# LCD.net
KiCad netlist of a schematic drawn in Altium Designer
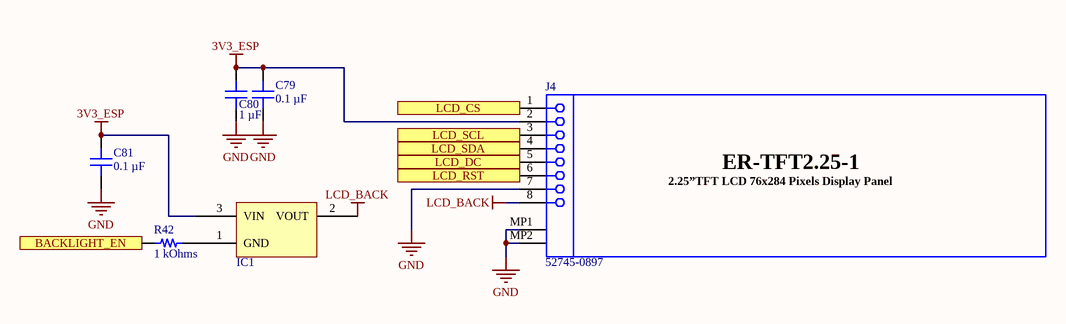
[diagram p0: LCD.SchDoc]

(export (version "E")
  (design (tool "Eeschema 10.0.6"))
  (components
    (comp (ref "C79")
      (value "0.1 µF")
      (footprint "CAP 0603_1608")
      (description "SMT Capacitor")
      (fields (field (name "PART NUMBER") "C0603C104M5RACTU") (field (name "MANUFACTURER") "KEMET"))
      (libsource (lib "Altium DB") (part "Capacitor"))
    )
    (comp (ref "C80")
      (value "1 µF")
      (footprint "CAP 0603_1608")
      (description "SMT Capacitor")
      (fields
        (field (name "PART NUMBER") "GMC10X7R105M50NT")
        (field (name "MANUFACTURER") "Cal-Chip Electronics, Inc.")
      )
      (libsource (lib "Altium DB") (part "Capacitor"))
    )
    (comp (ref "C81")
      (value "0.1 µF")
      (footprint "CAP 0603_1608")
      (description "SMT Capacitor")
      (fields (field (name "PART NUMBER") "C0603C104M5RACTU") (field (name "MANUFACTURER") "KEMET"))
      (libsource (lib "Altium DB") (part "Capacitor"))
    )
    (comp (ref "IC1")
      (value "Taken From Chinese PCB")
      (footprint "DIODES SOT-23-3")
      (description "IC REG LINEAR LED DRIVER 60mA")
      (fields (field (name "MANUFACTURER") "Diodes Incorporated"))
      (libsource (lib "Altium DB") (part "Diodes Inc AP7313R"))
    )
    (comp (ref "J4")
      (value "52745-0897")
      (footprint "MOLX-52745-0897")
      (fields (field (name "MANUFACTURER") "Molex"))
      (libsource (lib "Lib") (part "52745-0897"))
    )
    (comp (ref "R42")
      (value "1 kOhms")
      (footprint "RES 0603_1608")
      (description "RES SMD 1K OHM 1% 1/3W 0603")
      (fields
        (field (name "MANUFACTURER") "Panasonic Electronic Components")
        (field (name "PART NUMBER") "ERJ-PA3F1001V")
      )
      (libsource (lib "Altium DB") (part "Resistor"))
    )
  )
  (nets
    (net (code "1") (name "/BACKLIGHT_EN") (class "Default")
      (node (ref "R42") (pin "2") (pinfunction "2_2") (pintype "passive"))
    )
    (net (code "2") (name "/LCD_CS") (class "Default")
      (node (ref "J4") (pin "1") (pinfunction "1_1") (pintype "passive"))
    )
    (net (code "3") (name "/LCD_DC") (class "Default")
      (node (ref "J4") (pin "5") (pinfunction "5_5") (pintype "passive"))
    )
    (net (code "4") (name "/LCD_RST") (class "Default")
      (node (ref "J4") (pin "6") (pinfunction "6_6") (pintype "passive"))
    )
    (net (code "5") (name "/LCD_SCL") (class "Default")
      (node (ref "J4") (pin "3") (pinfunction "3_3") (pintype "passive"))
    )
    (net (code "6") (name "/LCD_SDA") (class "Default")
      (node (ref "J4") (pin "4") (pinfunction "4_4") (pintype "passive"))
    )
    (net (code "7") (name "3V3_ESP") (class "Default")
      (node (ref "C79") (pin "2") (pinfunction "2_2") (pintype "passive"))
      (node (ref "C80") (pin "2") (pinfunction "2_2") (pintype "passive"))
      (node (ref "C81") (pin "2") (pinfunction "2_2") (pintype "passive"))
      (node (ref "IC1") (pin "3") (pinfunction "VIN_3") (pintype "passive"))
      (node (ref "J4") (pin "2") (pinfunction "2_2") (pintype "passive"))
    )
    (net (code "8") (name "GND") (class "Default")
      (node (ref "C79") (pin "1") (pinfunction "1_1") (pintype "passive"))
      (node (ref "C80") (pin "1") (pinfunction "1_1") (pintype "passive"))
      (node (ref "C81") (pin "1") (pinfunction "1_1") (pintype "passive"))
      (node (ref "J4") (pin "7") (pinfunction "7_7") (pintype "passive"))
      (node (ref "J4") (pin "MP1") (pinfunction "MP1_MP1") (pintype "passive"))
      (node (ref "J4") (pin "MP2") (pinfunction "MP2_MP2") (pintype "passive"))
    )
    (net (code "9") (name "LCD_BACK") (class "Default")
      (node (ref "IC1") (pin "2") (pinfunction "VOUT_2") (pintype "passive"))
      (node (ref "J4") (pin "8") (pinfunction "8_8") (pintype "passive"))
    )
    (net (code "10") (name "Net-(IC1-GND)") (class "Default")
      (node (ref "IC1") (pin "1") (pinfunction "GND_1") (pintype "passive"))
      (node (ref "R42") (pin "1") (pinfunction "1_1") (pintype "passive"))
    )
  )
)
